# PowerSupply.net
KiCad netlist of a schematic drawn in Altium Designer
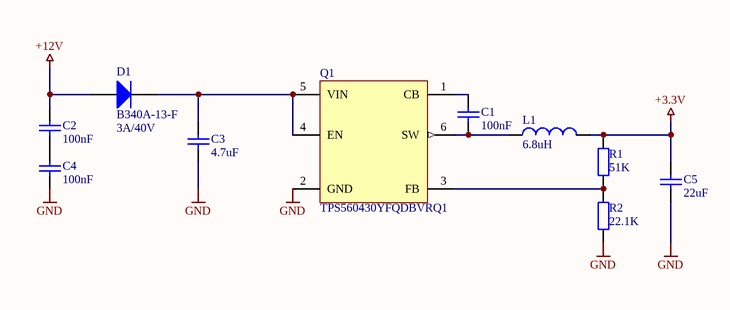
[diagram p0: PowerSupply.SchDoc]

(export (version "E")
  (design (tool "Eeschema 10.0.6"))
  (components
    (comp (ref "C1")
      (value "100nF")
      (footprint "CAPC1608X08N")
      (description "0603 Capacitor, 100nF")
      (fields (field (name "Comment") "CGA3E2X7R1H104K080AA"))
      (libsource (lib "Alt") (part "C0603-100nF-50V"))
    )
    (comp (ref "C2")
      (value "100nF")
      (footprint "CAPC1608X08N")
      (description "0603 Capacitor, 100nF")
      (fields (field (name "Comment") "CGA3E2X7R1H104K080AA"))
      (libsource (lib "Alt") (part "C0603-100nF-50V"))
    )
    (comp (ref "C3")
      (value "4.7uF")
      (footprint "CAPC2012X14N")
      (description "0805 Capacitor, 4.7uF")
      (fields (field (name "Comment") "CGA4J3X5R1H475K125AB"))
      (libsource (lib "Alt") (part "C0805-4.7uF-50V"))
    )
    (comp (ref "C4")
      (value "100nF")
      (footprint "CAPC1608X08N")
      (description "0603 Capacitor, 100nF")
      (fields (field (name "Comment") "CGA3E2X7R1H104K080AA"))
      (libsource (lib "Alt") (part "C0603-100nF-50V"))
    )
    (comp (ref "C5")
      (value "22uF")
      (footprint "CAPC3225X28N")
      (description "1210 Capacitor, 22uF")
      (fields (field (name "Comment") "CGA6P1X7R1C226M250AC"))
      (libsource (lib "Alt") (part "C1210-22uF-16V"))
    )
    (comp (ref "D1")
      (value "B340A-13-F")
      (footprint "DIOM4326X24N")
      (description "Schottky Diode, 3A, 40A")
      (fields (field (name "ALTIUM_VALUE") "3A/40V"))
      (libsource (lib "Alt") (part "D-SCH-3A-40V"))
    )
    (comp (ref "L1")
      (value "6.8uH")
      (footprint "INDP3532X20N")
      (description "Inductor 6.8uH, 1.9A, 2.2A Isat")
      (fields (field (name "Comment") "SRP3020TA-6R8M"))
      (libsource (lib "Alt") (part "IND-6.8uH-1.9A"))
    )
    (comp (ref "Q1")
      (value "TPS560430YFQDBVRQ1")
      (footprint "SOT95P280X110-6N")
      (description "TPS560430-Q1 SIMPLE SWITCHER 4-V to 36-V, 600-mA Synchronous Buck Converter")
      (libsource (lib "Alt") (part "TPS560430YF"))
    )
    (comp (ref "R1")
      (value "51K")
      (footprint "RESC1608X04N")
      (description "0603 Resistor")
      (fields (field (name "Comment") "ERJ-3EKF5102V"))
      (libsource (lib "Alt") (part "R0603R51K"))
    )
    (comp (ref "R2")
      (value "22.1K")
      (footprint "RESC1608X04N")
      (description "0603 Resistor")
      (fields (field (name "Comment") "ERJ-3EKF2212V"))
      (libsource (lib "Alt") (part "R0603R22.1K"))
    )
  )
  (nets
    (net (code "1") (name "+3.3V") (class "Default")
      (node (ref "C5") (pin "2") (pinfunction "2_2") (pintype "passive"))
      (node (ref "L1") (pin "2") (pinfunction "2_2") (pintype "passive"))
      (node (ref "R1") (pin "2") (pinfunction "2_2") (pintype "passive"))
    )
    (net (code "2") (name "+12V") (class "Default")
      (node (ref "C2") (pin "2") (pinfunction "2_2") (pintype "passive"))
      (node (ref "D1") (pin "1") (pinfunction "A_1") (pintype "passive"))
    )
    (net (code "3") (name "GND") (class "Default")
      (node (ref "C3") (pin "1") (pinfunction "1_1") (pintype "passive"))
      (node (ref "C4") (pin "1") (pinfunction "1_1") (pintype "passive"))
      (node (ref "C5") (pin "1") (pinfunction "1_1") (pintype "passive"))
      (node (ref "Q1") (pin "2") (pinfunction "GND_2") (pintype "power_in"))
      (node (ref "R2") (pin "1") (pinfunction "1_1") (pintype "passive"))
    )
    (net (code "4") (name "Net-(C2-Pad1)") (class "Default")
      (node (ref "C2") (pin "1") (pinfunction "1_1") (pintype "passive"))
      (node (ref "C4") (pin "2") (pinfunction "2_2") (pintype "passive"))
    )
    (net (code "5") (name "Net-(D1-K)") (class "Default")
      (node (ref "C3") (pin "2") (pinfunction "2_2") (pintype "passive"))
      (node (ref "D1") (pin "2") (pinfunction "K_2") (pintype "passive"))
      (node (ref "Q1") (pin "4") (pinfunction "EN_4") (pintype "passive"))
      (node (ref "Q1") (pin "5") (pinfunction "VIN_5") (pintype "power_in"))
    )
    (net (code "6") (name "Net-(Q1-CB)") (class "Default")
      (node (ref "C1") (pin "2") (pinfunction "2_2") (pintype "passive"))
      (node (ref "Q1") (pin "1") (pinfunction "CB_1") (pintype "passive"))
    )
    (net (code "7") (name "Net-(Q1-FB)") (class "Default")
      (node (ref "Q1") (pin "3") (pinfunction "FB_3") (pintype "passive"))
      (node (ref "R1") (pin "1") (pinfunction "1_1") (pintype "passive"))
      (node (ref "R2") (pin "2") (pinfunction "2_2") (pintype "passive"))
    )
    (net (code "8") (name "Net-(Q1-SW)") (class "Default")
      (node (ref "C1") (pin "1") (pinfunction "1_1") (pintype "passive"))
      (node (ref "L1") (pin "1") (pinfunction "1_1") (pintype "passive"))
      (node (ref "Q1") (pin "6") (pinfunction "SW_6") (pintype "output"))
    )
  )
)
